# ProDoc__-2026-03-25.net
KiCad netlist of a schematic drawn in EasyEDA Pro
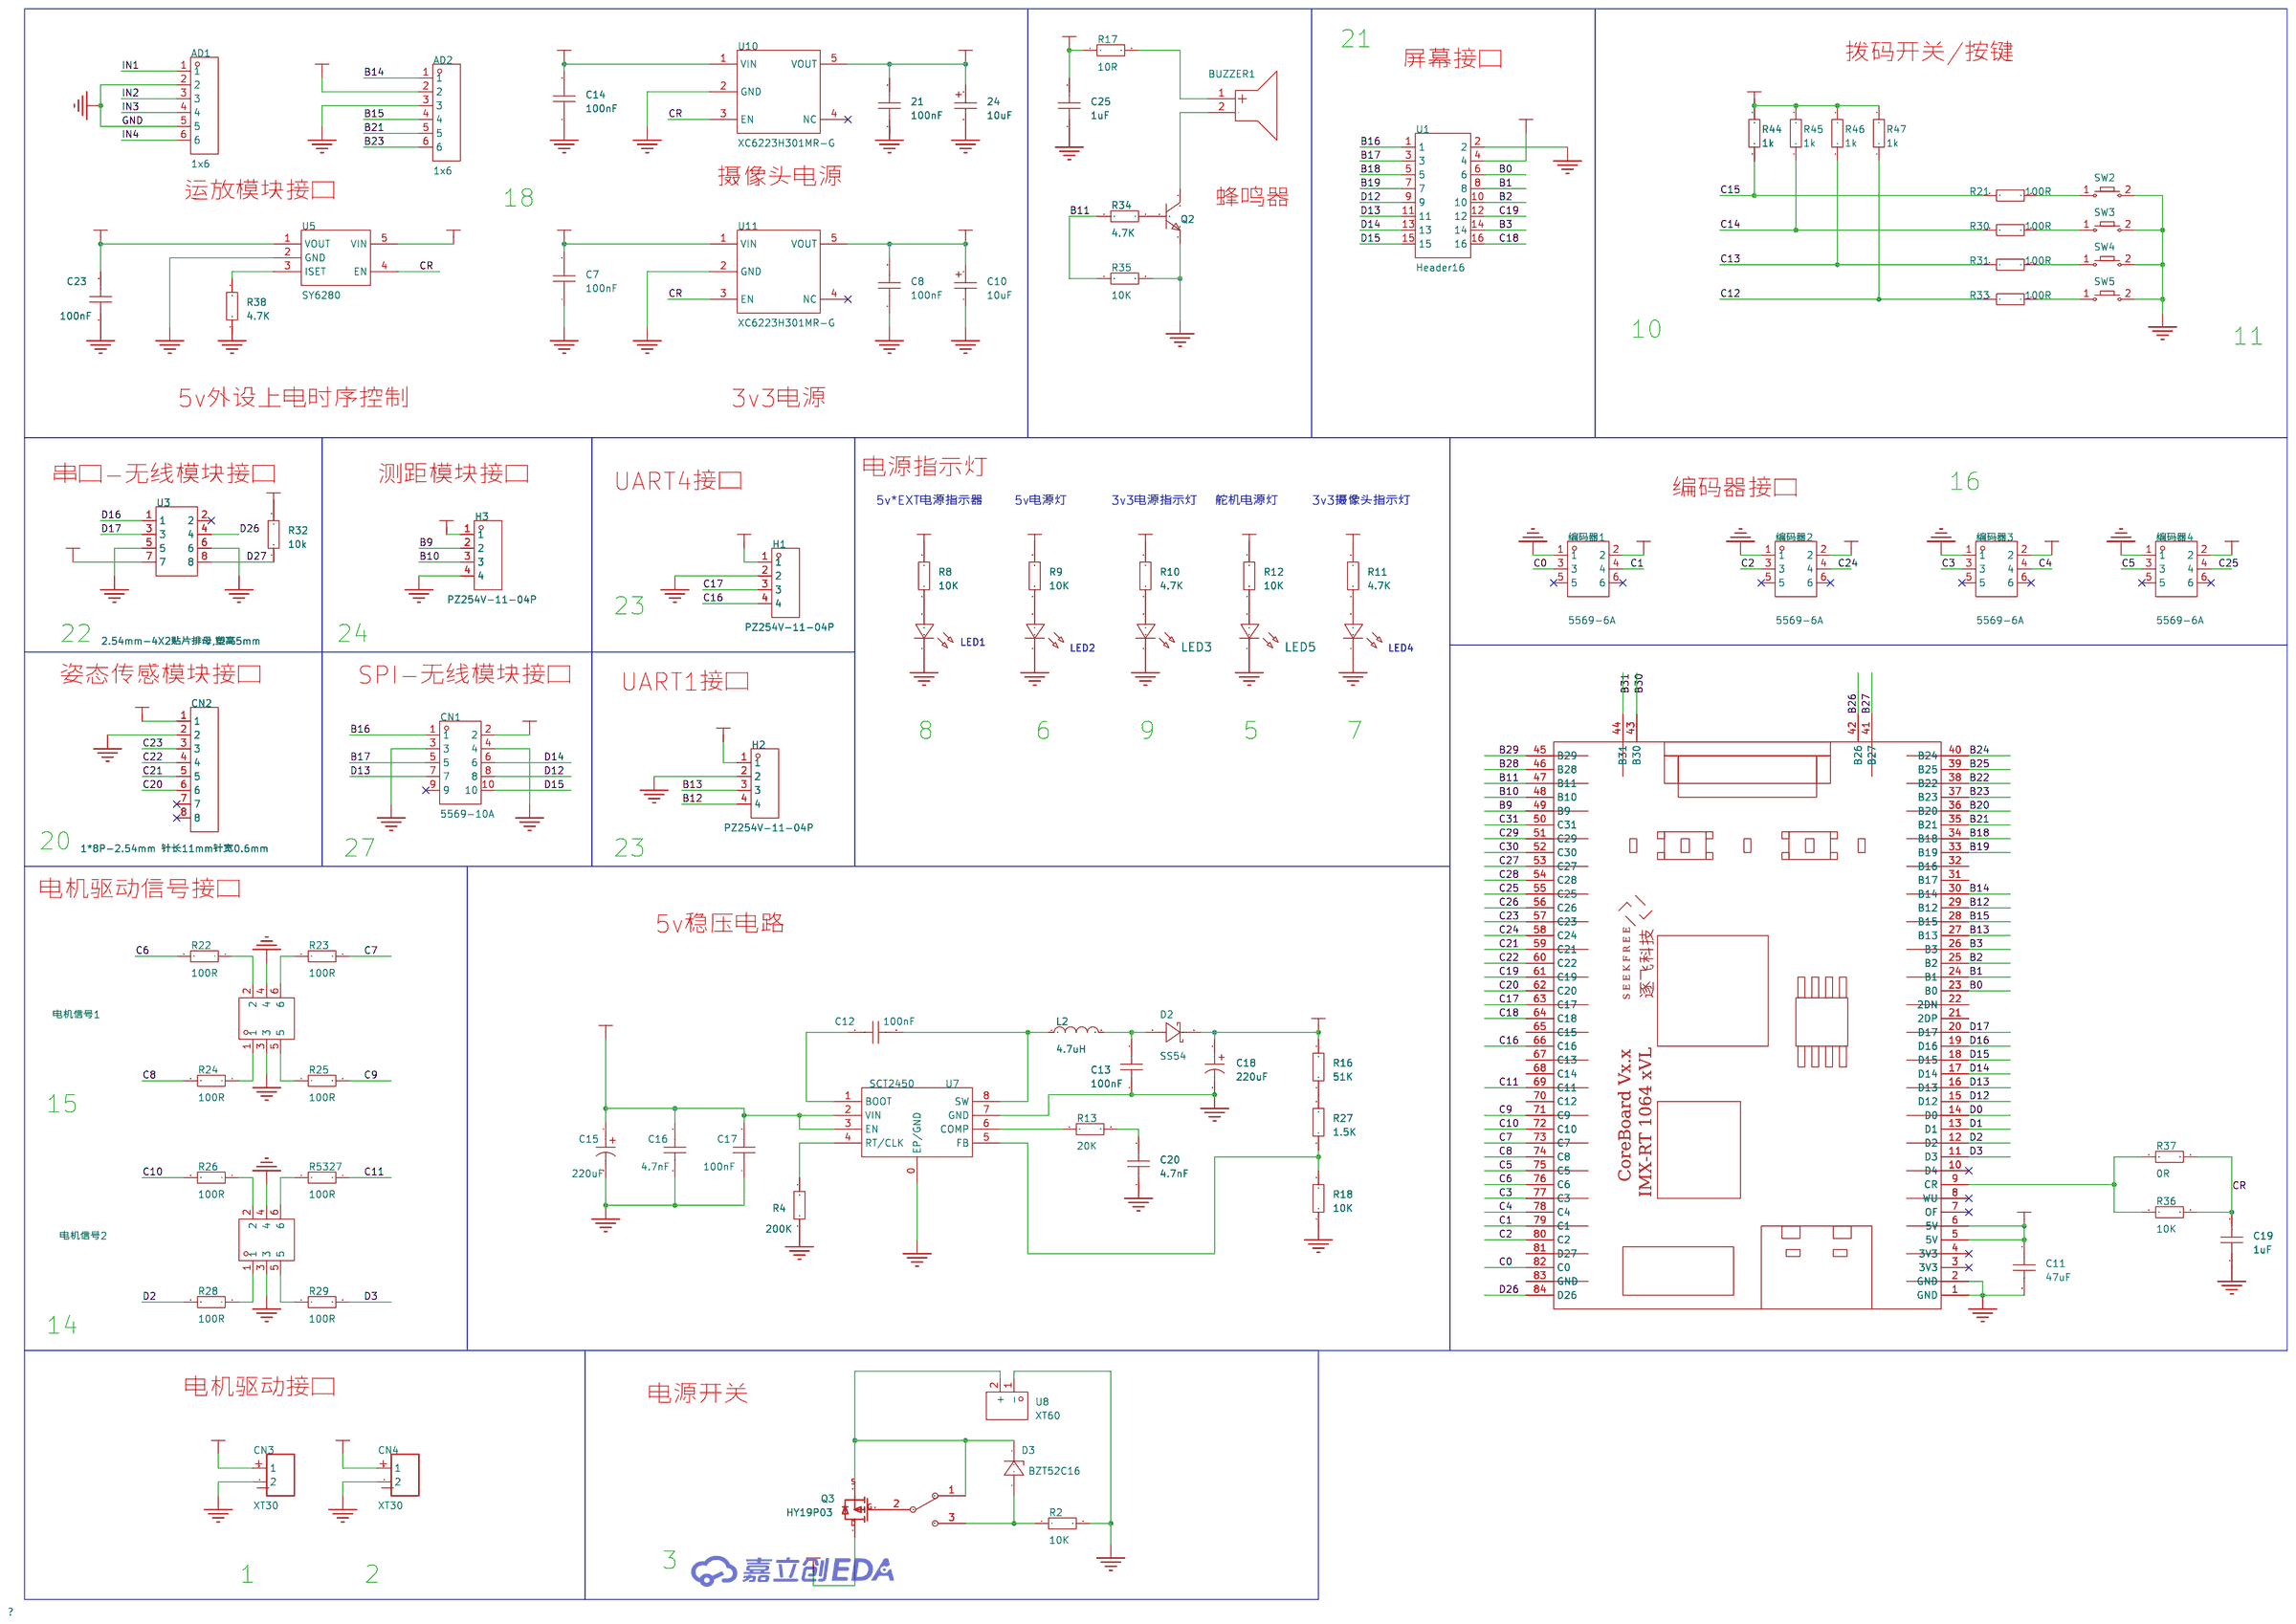
[diagram p0: schematic sheet]

(export (version "E")
  (design (tool "Eeschema 10.0.6"))
  (components
    (comp (ref "21")
      (value "100nF")
      (footprint "easyedapro:C0603")
      (libsource (lib "easyedapro") (part "Capacitance"))
    )
    (comp (ref "24")
      (value "10uF")
      (footprint "easyedapro:CAP-SMD_L3.2-W1.6-RD-C7171")
      (description "容值:10uF;精度:±10%;额定电压:16V;等效串联电阻(ESR):3Ω@100kHz;")
      (fields (field (name "Manufacturer Part") "TAJA106K016RNJ") (field (name "Manufacturer") "Kyocera AVX"))
      (libsource (lib "easyedapro") (part "TAJA106K016RNJ"))
    )
    (comp (ref "AD1")
      (value "1x6")
      (footprint "easyedapro:HDR-TH_6P-P2.54-V-F")
      (fields (field (name "Manufacturer Part") "Female header 1*6p") (field (name "Manufacturer") "BOOMELE"))
      (libsource (lib "easyedapro") (part "1x6"))
    )
    (comp (ref "AD2")
      (value "1x6")
      (footprint "easyedapro:HDR-TH_6P-P2.54-V-F")
      (fields (field (name "Manufacturer Part") "Female header 1*6p") (field (name "Manufacturer") "BOOMELE"))
      (libsource (lib "easyedapro") (part "1x6"))
    )
    (comp (ref "BUZZER1")
      (value "5V,管脚间距8mm,外径10mm,高9.5mm")
      (footprint "easyedapro:BUZ-TH_BD12.0-P7.60-D0.6-FD")
      (libsource (lib "easyedapro") (part "5V,管脚间距8MM,外径10MM,高9.5MM"))
    )
    (comp (ref "C7")
      (value "100nF")
      (footprint "easyedapro:C0603")
      (libsource (lib "easyedapro") (part "Capacitance"))
    )
    (comp (ref "C8")
      (value "100nF")
      (footprint "easyedapro:C0603")
      (libsource (lib "easyedapro") (part "Capacitance"))
    )
    (comp (ref "C10")
      (value "10uF")
      (footprint "easyedapro:CAP-SMD_L3.2-W1.6-RD-C7171")
      (description "容值:10uF;精度:±10%;额定电压:16V;等效串联电阻(ESR):3Ω@100kHz;")
      (fields (field (name "Manufacturer Part") "TAJA106K016RNJ") (field (name "Manufacturer") "Kyocera AVX"))
      (libsource (lib "easyedapro") (part "TAJA106K016RNJ"))
    )
    (comp (ref "C11")
      (value "47uF")
      (footprint "easyedapro:C0603")
      (libsource (lib "easyedapro") (part "Capacitance"))
    )
    (comp (ref "C12")
      (value "100nF")
      (footprint "easyedapro:C0603")
      (libsource (lib "easyedapro") (part "Capacitance"))
    )
    (comp (ref "C13")
      (value "100nF")
      (footprint "easyedapro:C1206")
      (libsource (lib "easyedapro") (part "Capacitance"))
    )
    (comp (ref "C14")
      (value "100nF")
      (footprint "easyedapro:C0603")
      (libsource (lib "easyedapro") (part "Capacitance"))
    )
    (comp (ref "C15")
      (value "220uF")
      (footprint "easyedapro:CAP-SMD_BD8.0-L8.3-W8.3-LS9.0-FD")
      (description "容值:220uF;精度:±20%;额定电压:25V;纹波电流:183mA@120Hz;")
      (fields
        (field (name "Manufacturer Part") "RYRVT25V220UF8*10")
        (field (name "Manufacturer") "HONOR(荣誉)")
      )
      (libsource (lib "easyedapro") (part "RYRVT25V220UF8*10"))
    )
    (comp (ref "C16")
      (value "4.7nF")
      (footprint "easyedapro:C1206")
      (libsource (lib "easyedapro") (part "Capacitance"))
    )
    (comp (ref "C17")
      (value "100nF")
      (footprint "easyedapro:C0603")
      (libsource (lib "easyedapro") (part "Capacitance"))
    )
    (comp (ref "C18")
      (value "220uF")
      (footprint "easyedapro:CAP-SMD_BD8.0-L8.3-W8.3-LS9.0-FD")
      (description "容值:220uF;精度:±20%;额定电压:25V;纹波电流:183mA@120Hz;")
      (fields
        (field (name "Manufacturer Part") "RYRVT25V220UF8*10")
        (field (name "Manufacturer") "HONOR(荣誉)")
      )
      (libsource (lib "easyedapro") (part "RYRVT25V220UF8*10"))
    )
    (comp (ref "C19")
      (value "1uF")
      (footprint "easyedapro:C0603")
      (libsource (lib "easyedapro") (part "Capacitance"))
    )
    (comp (ref "C20")
      (value "4.7nF")
      (footprint "easyedapro:C0603")
      (libsource (lib "easyedapro") (part "Capacitance"))
    )
    (comp (ref "C23")
      (value "100nF")
      (footprint "easyedapro:C0603")
      (libsource (lib "easyedapro") (part "Capacitance"))
    )
    (comp (ref "C25")
      (value "1uF")
      (footprint "easyedapro:C0603")
      (libsource (lib "easyedapro") (part "Capacitance"))
    )
    (comp (ref "CN1")
      (value "5569-10A")
      (footprint "easyedapro:CONN-TH_10P-P4.20_5569-10A")
      (libsource (lib "easyedapro") (part "5569-10A"))
    )
    (comp (ref "CN2")
      (value "1*8P-2.54mm 针长11mm针宽0.6mm")
      (footprint "easyedapro:HDR-TH_8P-P2.54-V-F-S2.54")
      (libsource (lib "easyedapro") (part "1*8P-2.54MM 针长11MM针宽0.6MM"))
    )
    (comp (ref "CN3")
      (value "XT30")
      (footprint "easyedapro:XT30 -WS母头")
      (fields
        (field (name "Manufacturer Part") "XT30UPB-F")
        (field (name "Manufacturer") "Changzhou Amass Elec")
      )
      (libsource (lib "easyedapro") (part "XT30"))
    )
    (comp (ref "CN4")
      (value "XT30")
      (footprint "easyedapro:XT30 -WS母头")
      (fields
        (field (name "Manufacturer Part") "XT30UPB-F")
        (field (name "Manufacturer") "Changzhou Amass Elec")
      )
      (libsource (lib "easyedapro") (part "XT30"))
    )
    (comp (ref "D2")
      (value "SS54")
      (footprint "easyedapro:SMA_L4.2-W2.6-LS5.1-RD")
      (libsource (lib "easyedapro") (part "SS54_C9900023219"))
    )
    (comp (ref "D3")
      (value "BZT52C16")
      (footprint "easyedapro:SOD-123-L")
      (libsource (lib "easyedapro") (part "Diode Zen"))
    )
    (comp (ref "H1")
      (value "PZ254V-11-04P")
      (footprint "easyedapro:HDR-TH_4P-P2.54-V-M")
      (fields (field (name "Manufacturer") "XFCN(兴飞)"))
      (libsource (lib "easyedapro") (part "PZ254V-11-04P_C2691448"))
    )
    (comp (ref "H2")
      (value "PZ254V-11-04P")
      (footprint "easyedapro:HDR-TH_4P-P2.54-V-M")
      (fields (field (name "Manufacturer") "XFCN(兴飞)"))
      (libsource (lib "easyedapro") (part "PZ254V-11-04P_C2691448"))
    )
    (comp (ref "H3")
      (value "PZ254V-11-04P")
      (footprint "easyedapro:HDR-TH_4P-P2.54-V-M")
      (fields (field (name "Manufacturer") "XFCN(兴飞)"))
      (libsource (lib "easyedapro") (part "PZ254V-11-04P_C2691448"))
    )
    (comp (ref "L2")
      (value "4.7uH")
      (footprint "easyedapro:IND-SMD_L7.1-W6.6_POHS0603")
      (description "电感值:4.7uH;精度:±20%;额定电流:5A;饱和电流(Isat):8A;类型:一体成型电感;")
      (fields
        (field (name "Manufacturer Part") "POHS0603-4R7M")
        (field (name "Manufacturer") "HYHONGYEX(宏业)")
      )
      (libsource (lib "easyedapro") (part "POHS0603-4R7M"))
    )
    (comp (ref "LED1")
      (value "~")
      (footprint "easyedapro:LED_0603")
      (libsource (lib "easyedapro") (part "LED_G"))
    )
    (comp (ref "LED2")
      (value "~")
      (footprint "easyedapro:LED_0603")
      (libsource (lib "easyedapro") (part "LED_B"))
    )
    (comp (ref "LED3")
      (value "~")
      (footprint "easyedapro:LED_0603")
      (libsource (lib "easyedapro") (part "LED_R"))
    )
    (comp (ref "LED4")
      (value "~")
      (footprint "easyedapro:LED_0603")
      (libsource (lib "easyedapro") (part "LED_G"))
    )
    (comp (ref "LED5")
      (value "~")
      (footprint "easyedapro:LED_0603")
      (libsource (lib "easyedapro") (part "LED_R"))
    )
    (comp (ref "Q2")
      (value "~")
      (footprint "easyedapro:S8050_TO_92")
      (libsource (lib "easyedapro") (part "S8050_TO_NPN"))
    )
    (comp (ref "Q3")
      (value "HY19P03")
      (footprint "easyedapro:TO-252AA")
      (description "HY19P03 P-Channel MOSFET")
      (libsource (lib "easyedapro") (part "HY19P03"))
    )
    (comp (ref "R2") (value "10K") (footprint "easyedapro:R0603") (libsource (lib "easyedapro") (part "电阻")))
    (comp (ref "R4") (value "200K") (footprint "easyedapro:R0603") (libsource (lib "easyedapro") (part "电阻")))
    (comp (ref "R8") (value "10K") (footprint "easyedapro:R0603") (libsource (lib "easyedapro") (part "电阻")))
    (comp (ref "R9") (value "10K") (footprint "easyedapro:R0603") (libsource (lib "easyedapro") (part "电阻")))
    (comp (ref "R10")
      (value "4.7K")
      (footprint "easyedapro:R0603")
      (libsource (lib "easyedapro") (part "电阻"))
    )
    (comp (ref "R11")
      (value "4.7K")
      (footprint "easyedapro:R0603")
      (libsource (lib "easyedapro") (part "电阻"))
    )
    (comp (ref "R12") (value "10K") (footprint "easyedapro:R0603") (libsource (lib "easyedapro") (part "电阻")))
    (comp (ref "R13") (value "20K") (footprint "easyedapro:R0603") (libsource (lib "easyedapro") (part "电阻")))
    (comp (ref "R16") (value "51K") (footprint "easyedapro:R0603") (libsource (lib "easyedapro") (part "电阻")))
    (comp (ref "R17") (value "10R") (footprint "easyedapro:R0603") (libsource (lib "easyedapro") (part "电阻")))
    (comp (ref "R18") (value "10K") (footprint "easyedapro:R0603") (libsource (lib "easyedapro") (part "电阻")))
    (comp (ref "R21")
      (value "100Ω ±1% 62.5mW")
      (footprint "easyedapro:R0402")
      (fields
        (field (name "Manufacturer Part") "0402WGF1000TCE")
        (field (name "Manufacturer") "UNI-ROYAL(厚声)")
      )
      (libsource (lib "easyedapro") (part "0402WGF1000TCE"))
    )
    (comp (ref "R22")
      (value "100Ω ±1% 62.5mW")
      (footprint "easyedapro:R0402")
      (fields
        (field (name "Manufacturer Part") "0402WGF1000TCE")
        (field (name "Manufacturer") "UNI-ROYAL(厚声)")
      )
      (libsource (lib "easyedapro") (part "0402WGF1000TCE"))
    )
    (comp (ref "R23")
      (value "100Ω ±1% 62.5mW")
      (footprint "easyedapro:R0402")
      (fields
        (field (name "Manufacturer Part") "0402WGF1000TCE")
        (field (name "Manufacturer") "UNI-ROYAL(厚声)")
      )
      (libsource (lib "easyedapro") (part "0402WGF1000TCE"))
    )
    (comp (ref "R24")
      (value "100Ω ±1% 62.5mW")
      (footprint "easyedapro:R0402")
      (fields
        (field (name "Manufacturer Part") "0402WGF1000TCE")
        (field (name "Manufacturer") "UNI-ROYAL(厚声)")
      )
      (libsource (lib "easyedapro") (part "0402WGF1000TCE"))
    )
    (comp (ref "R25")
      (value "100Ω ±1% 62.5mW")
      (footprint "easyedapro:R0402")
      (fields
        (field (name "Manufacturer Part") "0402WGF1000TCE")
        (field (name "Manufacturer") "UNI-ROYAL(厚声)")
      )
      (libsource (lib "easyedapro") (part "0402WGF1000TCE"))
    )
    (comp (ref "R26")
      (value "100Ω ±1% 62.5mW")
      (footprint "easyedapro:R0402")
      (fields
        (field (name "Manufacturer Part") "0402WGF1000TCE")
        (field (name "Manufacturer") "UNI-ROYAL(厚声)")
      )
      (libsource (lib "easyedapro") (part "0402WGF1000TCE"))
    )
    (comp (ref "R27")
      (value "1.5K")
      (footprint "easyedapro:R0603")
      (libsource (lib "easyedapro") (part "电阻"))
    )
    (comp (ref "R28")
      (value "100Ω ±1% 62.5mW")
      (footprint "easyedapro:R0402")
      (fields
        (field (name "Manufacturer Part") "0402WGF1000TCE")
        (field (name "Manufacturer") "UNI-ROYAL(厚声)")
      )
      (libsource (lib "easyedapro") (part "0402WGF1000TCE"))
    )
    (comp (ref "R29")
      (value "100Ω ±1% 62.5mW")
      (footprint "easyedapro:R0402")
      (fields
        (field (name "Manufacturer Part") "0402WGF1000TCE")
        (field (name "Manufacturer") "UNI-ROYAL(厚声)")
      )
      (libsource (lib "easyedapro") (part "0402WGF1000TCE"))
    )
    (comp (ref "R30")
      (value "100Ω ±1% 62.5mW")
      (footprint "easyedapro:R0402")
      (fields
        (field (name "Manufacturer Part") "0402WGF1000TCE")
        (field (name "Manufacturer") "UNI-ROYAL(厚声)")
      )
      (libsource (lib "easyedapro") (part "0402WGF1000TCE"))
    )
    (comp (ref "R31")
      (value "100Ω ±1% 62.5mW")
      (footprint "easyedapro:R0402")
      (fields
        (field (name "Manufacturer Part") "0402WGF1000TCE")
        (field (name "Manufacturer") "UNI-ROYAL(厚声)")
      )
      (libsource (lib "easyedapro") (part "0402WGF1000TCE"))
    )
    (comp (ref "R32")
      (value "10k")
      (footprint "easyedapro:R0603")
      (description "电阻类型:厚膜电阻;阻值:10kΩ;精度:±1%;功率:100mW;工作电压:75V;温度系数:±100ppm/°C;")
      (fields
        (field (name "Manufacturer Part") "0603WAF1002T5E")
        (field (name "Manufacturer") "UNI-ROYAL(厚声)")
      )
      (libsource (lib "easyedapro") (part "0603WAF1002T5E"))
    )
    (comp (ref "R33")
      (value "100Ω ±1% 62.5mW")
      (footprint "easyedapro:R0402")
      (fields
        (field (name "Manufacturer Part") "0402WGF1000TCE")
        (field (name "Manufacturer") "UNI-ROYAL(厚声)")
      )
      (libsource (lib "easyedapro") (part "0402WGF1000TCE"))
    )
    (comp (ref "R34")
      (value "4.7K")
      (footprint "easyedapro:R0603")
      (libsource (lib "easyedapro") (part "电阻"))
    )
    (comp (ref "R35") (value "10K") (footprint "easyedapro:R0603") (libsource (lib "easyedapro") (part "电阻")))
    (comp (ref "R36") (value "10K") (footprint "easyedapro:R0603") (libsource (lib "easyedapro") (part "电阻")))
    (comp (ref "R37") (value "0R") (footprint "easyedapro:R0603") (libsource (lib "easyedapro") (part "电阻")))
    (comp (ref "R38")
      (value "4.7K")
      (footprint "easyedapro:R0603")
      (libsource (lib "easyedapro") (part "电阻"))
    )
    (comp (ref "R44")
      (value "1k")
      (footprint "easyedapro:R0603")
      (description "电阻类型:厚膜电阻;阻值:10kΩ;精度:±1%;功率:100mW;工作电压:75V;温度系数:±100ppm/°C;")
      (fields
        (field (name "Manufacturer Part") "0603WAF1002T5E")
        (field (name "Manufacturer") "UNI-ROYAL(厚声)")
      )
      (libsource (lib "easyedapro") (part "0603WAF1002T5E"))
    )
    (comp (ref "R45")
      (value "1k")
      (footprint "easyedapro:R0603")
      (description "电阻类型:厚膜电阻;阻值:10kΩ;精度:±1%;功率:100mW;工作电压:75V;温度系数:±100ppm/°C;")
      (fields
        (field (name "Manufacturer Part") "0603WAF1002T5E")
        (field (name "Manufacturer") "UNI-ROYAL(厚声)")
      )
      (libsource (lib "easyedapro") (part "0603WAF1002T5E"))
    )
    (comp (ref "R46")
      (value "1k")
      (footprint "easyedapro:R0603")
      (description "电阻类型:厚膜电阻;阻值:10kΩ;精度:±1%;功率:100mW;工作电压:75V;温度系数:±100ppm/°C;")
      (fields
        (field (name "Manufacturer Part") "0603WAF1002T5E")
        (field (name "Manufacturer") "UNI-ROYAL(厚声)")
      )
      (libsource (lib "easyedapro") (part "0603WAF1002T5E"))
    )
    (comp (ref "R47")
      (value "1k")
      (footprint "easyedapro:R0603")
      (description "电阻类型:厚膜电阻;阻值:10kΩ;精度:±1%;功率:100mW;工作电压:75V;温度系数:±100ppm/°C;")
      (fields
        (field (name "Manufacturer Part") "0603WAF1002T5E")
        (field (name "Manufacturer") "UNI-ROYAL(厚声)")
      )
      (libsource (lib "easyedapro") (part "0603WAF1002T5E"))
    )
    (comp (ref "R5327")
      (value "100Ω ±1% 62.5mW")
      (footprint "easyedapro:R0402")
      (fields
        (field (name "Manufacturer Part") "0402WGF1000TCE")
        (field (name "Manufacturer") "UNI-ROYAL(厚声)")
      )
      (libsource (lib "easyedapro") (part "0402WGF1000TCE"))
    )
    (comp (ref "SW2")
      (value "~")
      (footprint "easyedapro:Key_SMD_3x4x2")
      (libsource (lib "easyedapro") (part "轻触按键x2"))
    )
    (comp (ref "SW3")
      (value "~")
      (footprint "easyedapro:Key_SMD_3x4x2")
      (libsource (lib "easyedapro") (part "轻触按键x2"))
    )
    (comp (ref "SW4")
      (value "~")
      (footprint "easyedapro:Key_SMD_3x4x2")
      (libsource (lib "easyedapro") (part "轻触按键x2"))
    )
    (comp (ref "SW5")
      (value "~")
      (footprint "easyedapro:Key_SMD_3x4x2")
      (libsource (lib "easyedapro") (part "轻触按键x2"))
    )
    (comp (ref "SW6")
      (value "拨码开关")
      (footprint "easyedapro:3PIN2档拨动开关")
      (libsource (lib "easyedapro") (part "1路滑动开关"))
    )
    (comp (ref "U1")
      (value "Header16")
      (footprint "easyedapro:CONN-TH_16P-P2.50_C9900044747")
      (libsource (lib "easyedapro") (part "HEADER16_C9900044747"))
    )
    (comp (ref "U3")
      (value "2.54mm-4X2贴片排母,塑高5mm")
      (footprint "easyedapro:HDR-SMD_8P-P2.54-V-F-R2-C4-S7.1")
      (libsource (lib "easyedapro") (part "2.54MM-4X2贴片排母,塑高5MM"))
    )
    (comp (ref "U5")
      (value "SY6280")
      (footprint "easyedapro:SOT-23-5")
      (libsource (lib "easyedapro") (part "SY6280"))
    )
    (comp (ref "U7")
      (value "SCT2450")
      (footprint "easyedapro:SOP-8E")
      (libsource (lib "easyedapro") (part "SCT2450"))
    )
    (comp (ref "U8")
      (value "XT60")
      (footprint "easyedapro:CONN-TH_XT60")
      (description "模型锂电连接器")
      (fields (field (name "Manufacturer") "AMASS(艾迈斯)"))
      (libsource (lib "easyedapro") (part "XT60"))
    )
    (comp (ref "U10")
      (value "XC6223H301MR-G")
      (footprint "easyedapro:SOT_235")
      (libsource (lib "easyedapro") (part "RT9013"))
    )
    (comp (ref "U11")
      (value "XC6223H301MR-G")
      (footprint "easyedapro:SOT_235")
      (libsource (lib "easyedapro") (part "RT9013"))
    )
    (comp (ref "U?1")
      (value "~")
      (footprint "easyedapro:AUFE_RT1064")
      (libsource (lib "easyedapro") (part "RT1064"))
    )
    (comp (ref "电机信号1")
      (value "5569-6A")
      (footprint "easyedapro:CONN-TH_6P-P4.20_5569-6A-1")
      (libsource (lib "easyedapro") (part "5569-6A"))
    )
    (comp (ref "电机信号2")
      (value "5569-6A")
      (footprint "easyedapro:CONN-TH_6P-P4.20_5569-6A-1")
      (libsource (lib "easyedapro") (part "5569-6A"))
    )
    (comp (ref "编码器1")
      (value "5569-6A")
      (footprint "easyedapro:CONN-TH_6P-P4.20_5569-6A-1")
      (libsource (lib "easyedapro") (part "5569-6A"))
    )
    (comp (ref "编码器2")
      (value "5569-6A")
      (footprint "easyedapro:CONN-TH_6P-P4.20_5569-6A-1")
      (libsource (lib "easyedapro") (part "5569-6A"))
    )
    (comp (ref "编码器3")
      (value "5569-6A")
      (footprint "easyedapro:CONN-TH_6P-P4.20_5569-6A-1")
      (libsource (lib "easyedapro") (part "5569-6A"))
    )
    (comp (ref "编码器4")
      (value "5569-6A")
      (footprint "easyedapro:CONN-TH_6P-P4.20_5569-6A-1")
      (libsource (lib "easyedapro") (part "5569-6A"))
    )
  )
  (nets
    (net (code "1") (name "/B0") (class "Default")
      (node (ref "U1") (pin "6") (pinfunction "6_6") (pintype "unspecified"))
      (node (ref "U?1") (pin "23") (pinfunction "B0_23") (pintype "input"))
    )
    (net (code "2") (name "/B1") (class "Default")
      (node (ref "U1") (pin "8") (pinfunction "8_8") (pintype "unspecified"))
      (node (ref "U?1") (pin "24") (pinfunction "B1_24") (pintype "input"))
    )
    (net (code "3") (name "/B2") (class "Default")
      (node (ref "U1") (pin "10") (pinfunction "10_10") (pintype "unspecified"))
      (node (ref "U?1") (pin "25") (pinfunction "B2_25") (pintype "input"))
    )
    (net (code "4") (name "/B3") (class "Default")
      (node (ref "U1") (pin "14") (pinfunction "14_14") (pintype "unspecified"))
      (node (ref "U?1") (pin "26") (pinfunction "B3_26") (pintype "input"))
    )
    (net (code "5") (name "/B9") (class "Default")
      (node (ref "H3") (pin "2") (pinfunction "2_2") (pintype "unspecified"))
      (node (ref "U?1") (pin "49") (pinfunction "B9_49") (pintype "input"))
    )
    (net (code "6") (name "/B10") (class "Default")
      (node (ref "H3") (pin "3") (pinfunction "3_3") (pintype "unspecified"))
      (node (ref "U?1") (pin "48") (pinfunction "B10_48") (pintype "input"))
    )
    (net (code "7") (name "/B11") (class "Default")
      (node (ref "R34") (pin "1") (pinfunction "1_1") (pintype "input"))
      (node (ref "R35") (pin "1") (pinfunction "1_1") (pintype "input"))
      (node (ref "U?1") (pin "47") (pinfunction "B11_47") (pintype "input"))
    )
    (net (code "8") (name "/B12") (class "Default")
      (node (ref "H2") (pin "4") (pinfunction "4_4") (pintype "unspecified"))
      (node (ref "U?1") (pin "29") (pinfunction "B12_29") (pintype "input"))
    )
    (net (code "9") (name "/B13") (class "Default")
      (node (ref "H2") (pin "3") (pinfunction "3_3") (pintype "unspecified"))
      (node (ref "U?1") (pin "27") (pinfunction "B13_27") (pintype "input"))
    )
    (net (code "10") (name "/B14") (class "Default")
      (node (ref "AD2") (pin "1") (pinfunction "1_1") (pintype "unspecified"))
      (node (ref "U?1") (pin "30") (pinfunction "B14_30") (pintype "input"))
    )
    (net (code "11") (name "/B15") (class "Default")
      (node (ref "AD2") (pin "4") (pinfunction "4_4") (pintype "unspecified"))
      (node (ref "U?1") (pin "28") (pinfunction "B15_28") (pintype "input"))
    )
    (net (code "12") (name "/B16") (class "Default")
      (node (ref "CN1") (pin "1") (pinfunction "1_1") (pintype "unspecified"))
      (node (ref "U1") (pin "1") (pinfunction "1_1") (pintype "unspecified"))
    )
    (net (code "13") (name "/B17") (class "Default")
      (node (ref "CN1") (pin "5") (pinfunction "5_5") (pintype "unspecified"))
      (node (ref "U1") (pin "3") (pinfunction "3_3") (pintype "unspecified"))
    )
    (net (code "14") (name "/B18") (class "Default")
      (node (ref "U1") (pin "5") (pinfunction "5_5") (pintype "unspecified"))
      (node (ref "U?1") (pin "34") (pinfunction "B18_34") (pintype "input"))
    )
    (net (code "15") (name "/B19") (class "Default")
      (node (ref "U1") (pin "7") (pinfunction "7_7") (pintype "unspecified"))
      (node (ref "U?1") (pin "33") (pinfunction "B19_33") (pintype "input"))
    )
    (net (code "16") (name "/B20") (class "Default")
      (node (ref "U?1") (pin "36") (pinfunction "B20_36") (pintype "input"))
    )
    (net (code "17") (name "/B21") (class "Default")
      (node (ref "AD2") (pin "5") (pinfunction "5_5") (pintype "unspecified"))
      (node (ref "U?1") (pin "35") (pinfunction "B21_35") (pintype "input"))
    )
    (net (code "18") (name "/B22") (class "Default")
      (node (ref "U?1") (pin "38") (pinfunction "B22_38") (pintype "input"))
    )
    (net (code "19") (name "/B23") (class "Default")
      (node (ref "AD2") (pin "6") (pinfunction "6_6") (pintype "unspecified"))
      (node (ref "U?1") (pin "37") (pinfunction "B23_37") (pintype "input"))
    )
    (net (code "20") (name "/B24") (class "Default")
      (node (ref "U?1") (pin "40") (pinfunction "B24_40") (pintype "input"))
    )
    (net (code "21") (name "/B25") (class "Default")
      (node (ref "U?1") (pin "39") (pinfunction "B25_39") (pintype "input"))
    )
    (net (code "22") (name "/B26") (class "Default")
      (node (ref "U?1") (pin "42") (pinfunction "B26_42") (pintype "input"))
    )
    (net (code "23") (name "/B27") (class "Default")
      (node (ref "U?1") (pin "41") (pinfunction "B27_41") (pintype "input"))
    )
    (net (code "24") (name "/B28") (class "Default")
      (node (ref "U?1") (pin "46") (pinfunction "B28_46") (pintype "input"))
    )
    (net (code "25") (name "/B29") (class "Default")
      (node (ref "U?1") (pin "45") (pinfunction "B29_45") (pintype "input"))
    )
    (net (code "26") (name "/B30") (class "Default")
      (node (ref "U?1") (pin "43") (pinfunction "B30_43") (pintype "input"))
    )
    (net (code "27") (name "/B31") (class "Default")
      (node (ref "U?1") (pin "44") (pinfunction "B31_44") (pintype "input"))
    )
    (net (code "28") (name "/C0") (class "Default")
      (node (ref "U?1") (pin "82") (pinfunction "C0_82") (pintype "input"))
      (node (ref "编码器1") (pin "3") (pinfunction "3_3") (pintype "unspecified"))
    )
    (net (code "29") (name "/C1") (class "Default")
      (node (ref "U?1") (pin "79") (pinfunction "C1_79") (pintype "input"))
      (node (ref "编码器1") (pin "4") (pinfunction "4_4") (pintype "unspecified"))
    )
    (net (code "30") (name "/C2") (class "Default")
      (node (ref "U?1") (pin "80") (pinfunction "C2_80") (pintype "input"))
      (node (ref "编码器2") (pin "3") (pinfunction "3_3") (pintype "unspecified"))
    )
    (net (code "31") (name "/C3") (class "Default")
      (node (ref "U?1") (pin "77") (pinfunction "C3_77") (pintype "input"))
      (node (ref "编码器3") (pin "3") (pinfunction "3_3") (pintype "unspecified"))
    )
    (net (code "32") (name "/C4") (class "Default")
      (node (ref "U?1") (pin "78") (pinfunction "C4_78") (pintype "input"))
      (node (ref "编码器3") (pin "4") (pinfunction "4_4") (pintype "unspecified"))
    )
    (net (code "33") (name "/C5") (class "Default")
      (node (ref "U?1") (pin "75") (pinfunction "C5_75") (pintype "input"))
      (node (ref "编码器4") (pin "3") (pinfunction "3_3") (pintype "unspecified"))
    )
    (net (code "34") (name "/C6") (class "Default")
      (node (ref "R22") (pin "2") (pinfunction "2_2") (pintype "input"))
      (node (ref "U?1") (pin "76") (pinfunction "C6_76") (pintype "input"))
    )
    (net (code "35") (name "/C7") (class "Default")
      (node (ref "R23") (pin "1") (pinfunction "1_1") (pintype "input"))
      (node (ref "U?1") (pin "73") (pinfunction "C7_73") (pintype "input"))
    )
    (net (code "36") (name "/C8") (class "Default")
      (node (ref "R24") (pin "2") (pinfunction "2_2") (pintype "input"))
      (node (ref "U?1") (pin "74") (pinfunction "C8_74") (pintype "input"))
    )
    (net (code "37") (name "/C9") (class "Default")
      (node (ref "R25") (pin "2") (pinfunction "2_2") (pintype "input"))
      (node (ref "U?1") (pin "71") (pinfunction "C9_71") (pintype "input"))
    )
    (net (code "38") (name "/C10") (class "Default")
      (node (ref "R26") (pin "2") (pinfunction "2_2") (pintype "input"))
      (node (ref "U?1") (pin "72") (pinfunction "C10_72") (pintype "input"))
    )
    (net (code "39") (name "/C11") (class "Default")
      (node (ref "R5327") (pin "1") (pinfunction "1_1") (pintype "input"))
      (node (ref "U?1") (pin "69") (pinfunction "C11_69") (pintype "input"))
    )
    (net (code "40") (name "/C12") (class "Default")
      (node (ref "R33") (pin "2") (pinfunction "2_2") (pintype "input"))
      (node (ref "R47") (pin "1") (pinfunction "1_1") (pintype "input"))
    )
    (net (code "41") (name "/C13") (class "Default")
      (node (ref "R31") (pin "2") (pinfunction "2_2") (pintype "input"))
      (node (ref "R46") (pin "1") (pinfunction "1_1") (pintype "input"))
    )
    (net (code "42") (name "/C14") (class "Default")
      (node (ref "R30") (pin "2") (pinfunction "2_2") (pintype "input"))
      (node (ref "R45") (pin "1") (pinfunction "1_1") (pintype "input"))
    )
    (net (code "43") (name "/C15") (class "Default")
      (node (ref "R21") (pin "2") (pinfunction "2_2") (pintype "input"))
      (node (ref "R44") (pin "1") (pinfunction "1_1") (pintype "input"))
    )
    (net (code "44") (name "/C16") (class "Default")
      (node (ref "H1") (pin "4") (pinfunction "4_4") (pintype "unspecified"))
      (node (ref "U?1") (pin "66") (pinfunction "C16_66") (pintype "input"))
    )
    (net (code "45") (name "/C17") (class "Default")
      (node (ref "H1") (pin "3") (pinfunction "3_3") (pintype "unspecified"))
      (node (ref "U?1") (pin "63") (pinfunction "C17_63") (pintype "input"))
    )
    (net (code "46") (name "/C18") (class "Default")
      (node (ref "U1") (pin "16") (pinfunction "16_16") (pintype "unspecified"))
      (node (ref "U?1") (pin "64") (pinfunction "C18_64") (pintype "input"))
    )
    (net (code "47") (name "/C19") (class "Default")
      (node (ref "U1") (pin "12") (pinfunction "12_12") (pintype "unspecified"))
      (node (ref "U?1") (pin "61") (pinfunction "C19_61") (pintype "input"))
    )
    (net (code "48") (name "/C20") (class "Default")
      (node (ref "CN2") (pin "6") (pinfunction "6_6") (pintype "unspecified"))
      (node (ref "U?1") (pin "62") (pinfunction "C20_62") (pintype "input"))
    )
    (net (code "49") (name "/C21") (class "Default")
      (node (ref "CN2") (pin "5") (pinfunction "5_5") (pintype "unspecified"))
      (node (ref "U?1") (pin "59") (pinfunction "C21_59") (pintype "input"))
    )
    (net (code "50") (name "/C22") (class "Default")
      (node (ref "CN2") (pin "4") (pinfunction "4_4") (pintype "unspecified"))
      (node (ref "U?1") (pin "60") (pinfunction "C22_60") (pintype "input"))
    )
    (net (code "51") (name "/C23") (class "Default")
      (node (ref "CN2") (pin "3") (pinfunction "3_3") (pintype "unspecified"))
      (node (ref "U?1") (pin "57") (pinfunction "C23_57") (pintype "input"))
    )
    (net (code "52") (name "/C24") (class "Default")
      (node (ref "U?1") (pin "58") (pinfunction "C24_58") (pintype "input"))
      (node (ref "编码器2") (pin "4") (pinfunction "4_4") (pintype "unspecified"))
    )
    (net (code "53") (name "/C25") (class "Default")
      (node (ref "U?1") (pin "55") (pinfunction "C25_55") (pintype "input"))
      (node (ref "编码器4") (pin "4") (pinfunction "4_4") (pintype "unspecified"))
    )
    (net (code "54") (name "/C26") (class "Default")
      (node (ref "U?1") (pin "56") (pinfunction "C26_56") (pintype "input"))
    )
    (net (code "55") (name "/C27") (class "Default")
      (node (ref "U?1") (pin "53") (pinfunction "C27_53") (pintype "input"))
    )
    (net (code "56") (name "/C28") (class "Default")
      (node (ref "U?1") (pin "54") (pinfunction "C28_54") (pintype "input"))
    )
    (net (code "57") (name "/C29") (class "Default")
      (node (ref "U?1") (pin "51") (pinfunction "C29_51") (pintype "input"))
    )
    (net (code "58") (name "/C30") (class "Default")
      (node (ref "U?1") (pin "52") (pinfunction "C30_52") (pintype "input"))
    )
    (net (code "59") (name "/C31") (class "Default")
      (node (ref "U?1") (pin "50") (pinfunction "C31_50") (pintype "input"))
    )
    (net (code "60") (name "/CR") (class "Default")
      (node (ref "C19") (pin "2") (pinfunction "2_2") (pintype "input"))
      (node (ref "R36") (pin "2") (pinfunction "2_2") (pintype "input"))
      (node (ref "R37") (pin "2") (pinfunction "2_2") (pintype "input"))
      (node (ref "U10") (pin "3") (pinfunction "EN_3") (pintype "unspecified"))
      (node (ref "U11") (pin "3") (pinfunction "EN_3") (pintype "unspecified"))
      (node (ref "U5") (pin "4") (pinfunction "EN_4") (pintype "unspecified"))
    )
    (net (code "61") (name "/D0") (class "Default")
      (node (ref "U?1") (pin "14") (pinfunction "D0_14") (pintype "input"))
    )
    (net (code "62") (name "/D1") (class "Default")
      (node (ref "U?1") (pin "13") (pinfunction "D1_13") (pintype "input"))
    )
    (net (code "63") (name "/D2") (class "Default")
      (node (ref "R28") (pin "2") (pinfunction "2_2") (pintype "input"))
      (node (ref "U?1") (pin "12") (pinfunction "D2_12") (pintype "input"))
    )
    (net (code "64") (name "/D3") (class "Default")
      (node (ref "R29") (pin "2") (pinfunction "2_2") (pintype "input"))
      (node (ref "U?1") (pin "11") (pinfunction "D3_11") (pintype "input"))
    )
    (net (code "65") (name "/D12") (class "Default")
      (node (ref "CN1") (pin "8") (pinfunction "8_8") (pintype "unspecified"))
      (node (ref "U1") (pin "9") (pinfunction "9_9") (pintype "unspecified"))
      (node (ref "U?1") (pin "15") (pinfunction "D12_15") (pintype "input"))
    )
    (net (code "66") (name "/D13") (class "Default")
      (node (ref "CN1") (pin "7") (pinfunction "7_7") (pintype "unspecified"))
      (node (ref "U1") (pin "11") (pinfunction "11_11") (pintype "unspecified"))
      (node (ref "U?1") (pin "16") (pinfunction "D13_16") (pintype "input"))
    )
    (net (code "67") (name "/D14") (class "Default")
      (node (ref "CN1") (pin "6") (pinfunction "6_6") (pintype "unspecified"))
      (node (ref "U1") (pin "13") (pinfunction "13_13") (pintype "unspecified"))
      (node (ref "U?1") (pin "17") (pinfunction "D14_17") (pintype "input"))
    )
    (net (code "68") (name "/D15") (class "Default")
      (node (ref "CN1") (pin "10") (pinfunction "10_10") (pintype "unspecified"))
      (node (ref "U1") (pin "15") (pinfunction "15_15") (pintype "unspecified"))
      (node (ref "U?1") (pin "18") (pinfunction "D15_18") (pintype "input"))
    )
    (net (code "69") (name "/D16") (class "Default")
      (node (ref "U3") (pin "1") (pinfunction "1_1") (pintype "unspecified"))
      (node (ref "U?1") (pin "19") (pinfunction "D16_19") (pintype "input"))
    )
    (net (code "70") (name "/D17") (class "Default")
      (node (ref "U3") (pin "3") (pinfunction "3_3") (pintype "unspecified"))
      (node (ref "U?1") (pin "20") (pinfunction "D17_20") (pintype "input"))
    )
    (net (code "71") (name "/D26") (class "Default")
      (node (ref "U3") (pin "4") (pinfunction "4_4") (pintype "unspecified"))
      (node (ref "U?1") (pin "84") (pinfunction "D26_84") (pintype "input"))
    )
    (net (code "72") (name "/D27") (class "Default")
      (node (ref "R32") (pin "1") (pinfunction "1_1") (pintype "input"))
      (node (ref "U3") (pin "8") (pinfunction "8_8") (pintype "unspecified"))
    )
    (net (code "73") (name "/IN1") (class "Default")
      (node (ref "AD1") (pin "1") (pinfunction "1_1") (pintype "unspecified"))
    )
    (net (code "74") (name "/IN2") (class "Default")
      (node (ref "AD1") (pin "3") (pinfunction "3_3") (pintype "unspecified"))
    )
    (net (code "75") (name "/IN3") (class "Default")
      (node (ref "AD1") (pin "4") (pinfunction "4_4") (pintype "unspecified"))
    )
    (net (code "76") (name "/IN4") (class "Default")
      (node (ref "AD1") (pin "6") (pinfunction "6_6") (pintype "unspecified"))
    )
    (net (code "77") (name "3V3") (class "Default")
      (node (ref "21") (pin "2") (pinfunction "2_2") (pintype "input"))
      (node (ref "24") (pin "1") (pinfunction "1_1") (pintype "input"))
      (node (ref "AD2") (pin "2") (pinfunction "2_2") (pintype "unspecified"))
      (node (ref "C10") (pin "1") (pinfunction "1_1") (pintype "input"))
      (node (ref "C25") (pin "2") (pinfunction "2_2") (pintype "input"))
      (node (ref "C8") (pin "2") (pinfunction "2_2") (pintype "input"))
      (node (ref "CN2") (pin "1") (pinfunction "1_1") (pintype "unspecified"))
      (node (ref "H3") (pin "1") (pinfunction "1_1") (pintype "unspecified"))
      (node (ref "R10") (pin "2") (pinfunction "2_2") (pintype "input"))
      (node (ref "R17") (pin "1") (pinfunction "1_1") (pintype "input"))
      (node (ref "R32") (pin "2") (pinfunction "2_2") (pintype "input"))
      (node (ref "R44") (pin "2") (pinfunction "2_2") (pintype "input"))
      (node (ref "R45") (pin "2") (pinfunction "2_2") (pintype "input"))
      (node (ref "R46") (pin "2") (pinfunction "2_2") (pintype "input"))
      (node (ref "R47") (pin "2") (pinfunction "2_2") (pintype "input"))
      (node (ref "U1") (pin "4") (pinfunction "4_4") (pintype "unspecified"))
      (node (ref "U10") (pin "5") (pinfunction "VOUT_5") (pintype "unspecified"))
      (node (ref "U11") (pin "5") (pinfunction "VOUT_5") (pintype "unspecified"))
      (node (ref "编码器1") (pin "2") (pinfunction "2_2") (pintype "unspecified"))
      (node (ref "编码器2") (pin "2") (pinfunction "2_2") (pintype "unspecified"))
      (node (ref "编码器3") (pin "2") (pinfunction "2_2") (pintype "unspecified"))
      (node (ref "编码器4") (pin "2") (pinfunction "2_2") (pintype "unspecified"))
    )
    (net (code "78") (name "CSI-3V3") (class "Default")
      (node (ref "R11") (pin "2") (pinfunction "2_2") (pintype "input"))
    )
    (net (code "79") (name "GND") (class "Default")
      (node (ref "21") (pin "1") (pinfunction "1_1") (pintype "input"))
      (node (ref "24") (pin "2") (pinfunction "2_2") (pintype "input"))
      (node (ref "AD1") (pin "2") (pinfunction "2_2") (pintype "unspecified"))
      (node (ref "AD1") (pin "5") (pinfunction "5_5") (pintype "unspecified"))
      (node (ref "AD2") (pin "3") (pinfunction "3_3") (pintype "unspecified"))
      (node (ref "C10") (pin "2") (pinfunction "2_2") (pintype "input"))
      (node (ref "C11") (pin "2") (pinfunction "2_2") (pintype "input"))
      (node (ref "C13") (pin "1") (pinfunction "1_1") (pintype "input"))
      (node (ref "C14") (pin "1") (pinfunction "1_1") (pintype "input"))
      (node (ref "C15") (pin "2") (pinfunction "2_2") (pintype "input"))
      (node (ref "C16") (pin "1") (pinfunction "1_1") (pintype "input"))
      (node (ref "C17") (pin "1") (pinfunction "1_1") (pintype "input"))
      (node (ref "C18") (pin "2") (pinfunction "2_2") (pintype "input"))
      (node (ref "C19") (pin "1") (pinfunction "1_1") (pintype "input"))
      (node (ref "C20") (pin "1") (pinfunction "1_1") (pintype "input"))
      (node (ref "C23") (pin "1") (pinfunction "1_1") (pintype "input"))
      (node (ref "C25") (pin "1") (pinfunction "1_1") (pintype "input"))
      (node (ref "C7") (pin "1") (pinfunction "1_1") (pintype "input"))
      (node (ref "C8") (pin "1") (pinfunction "1_1") (pintype "input"))
      (node (ref "CN1") (pin "3") (pinfunction "3_3") (pintype "unspecified"))
      (node (ref "CN1") (pin "4") (pinfunction "4_4") (pintype "unspecified"))
      (node (ref "CN2") (pin "2") (pinfunction "2_2") (pintype "unspecified"))
      (node (ref "CN3") (pin "2") (pinfunction "2_2") (pintype "unspecified"))
      (node (ref "CN4") (pin "2") (pinfunction "2_2") (pintype "unspecified"))
      (node (ref "H1") (pin "2") (pinfunction "2_2") (pintype "unspecified"))
      (node (ref "H2") (pin "2") (pinfunction "2_2") (pintype "unspecified"))
      (node (ref "H3") (pin "4") (pinfunction "4_4") (pintype "unspecified"))
      (node (ref "LED1") (pin "1") (pinfunction "C_1") (pintype "input"))
      (node (ref "LED2") (pin "1") (pinfunction "C_1") (pintype "input"))
      (node (ref "LED3") (pin "1") (pinfunction "C_1") (pintype "input"))
      (node (ref "LED4") (pin "1") (pinfunction "C_1") (pintype "input"))
      (node (ref "LED5") (pin "1") (pinfunction "C_1") (pintype "input"))
      (node (ref "Q2") (pin "1") (pinfunction "E_1") (pintype "unspecified"))
      (node (ref "R18") (pin "1") (pinfunction "1_1") (pintype "input"))
      (node (ref "R2") (pin "2") (pinfunction "2_2") (pintype "input"))
      (node (ref "R35") (pin "2") (pinfunction "2_2") (pintype "input"))
      (node (ref "R38") (pin "1") (pinfunction "1_1") (pintype "input"))
      (node (ref "R4") (pin "1") (pinfunction "1_1") (pintype "input"))
      (node (ref "SW2") (pin "2") (pinfunction "2_2") (pintype "input"))
      (node (ref "SW3") (pin "2") (pinfunction "2_2") (pintype "input"))
      (node (ref "SW4") (pin "2") (pinfunction "2_2") (pintype "input"))
      (node (ref "SW5") (pin "2") (pinfunction "2_2") (pintype "input"))
      (node (ref "U1") (pin "2") (pinfunction "2_2") (pintype "unspecified"))
      (node (ref "U10") (pin "2") (pinfunction "GND_2") (pintype "unspecified"))
      (node (ref "U11") (pin "2") (pinfunction "GND_2") (pintype "unspecified"))
      (node (ref "U3") (pin "5") (pinfunction "5_5") (pintype "unspecified"))
      (node (ref "U3") (pin "6") (pinfunction "6_6") (pintype "unspecified"))
      (node (ref "U5") (pin "2") (pinfunction "GND_2") (pintype "unspecified"))
      (node (ref "U7") (pin "0") (pinfunction "EP/GND_0") (pintype "unspecified"))
      (node (ref "U7") (pin "7") (pinfunction "GND_7") (pintype "unspecified"))
      (node (ref "U8") (pin "1") (pinfunction "-_1") (pintype "input"))
      (node (ref "U?1") (pin "1") (pinfunction "GND_1") (pintype "input"))
      (node (ref "U?1") (pin "2") (pinfunction "GND_2") (pintype "input"))
      (node (ref "电机信号1") (pin "3") (pinfunction "3_3") (pintype "unspecified"))
      (node (ref "电机信号1") (pin "4") (pinfunction "4_4") (pintype "unspecified"))
      (node (ref "电机信号2") (pin "3") (pinfunction "3_3") (pintype "unspecified"))
      (node (ref "电机信号2") (pin "4") (pinfunction "4_4") (pintype "unspecified"))
      (node (ref "编码器1") (pin "1") (pinfunction "1_1") (pintype "unspecified"))
      (node (ref "编码器2") (pin "1") (pinfunction "1_1") (pintype "unspecified"))
      (node (ref "编码器3") (pin "1") (pinfunction "1_1") (pintype "unspecified"))
      (node (ref "编码器4") (pin "1") (pinfunction "1_1") (pintype "unspecified"))
    )
    (net (code "80") (name "Net-(BUZZER1-+)") (class "Default")
      (node (ref "BUZZER1") (pin "1") (pinfunction "+_1") (pintype "unspecified"))
      (node (ref "R17") (pin "2") (pinfunction "2_2") (pintype "input"))
    )
    (net (code "81") (name "Net-(BUZZER1--)") (class "Default")
      (node (ref "BUZZER1") (pin "2") (pinfunction "-_2") (pintype "unspecified"))
      (node (ref "Q2") (pin "3") (pinfunction "C_3") (pintype "unspecified"))
    )
    (net (code "82") (name "Net-(C20-Pad2)") (class "Default")
      (node (ref "C20") (pin "2") (pinfunction "2_2") (pintype "input"))
      (node (ref "R13") (pin "2") (pinfunction "2_2") (pintype "input"))
    )
    (net (code "83") (name "Net-(D2-A)") (class "Default")
      (node (ref "C13") (pin "2") (pinfunction "2_2") (pintype "input"))
      (node (ref "D2") (pin "2") (pinfunction "A_2") (pintype "unspecified"))
      (node (ref "L2") (pin "2") (pinfunction "2_2") (pintype "unspecified"))
    )
    (net (code "84") (name "Net-(D3-PadA)") (class "Default")
      (node (ref "D3") (pin "A") (pinfunction "A_A") (pintype "unspecified"))
      (node (ref "R2") (pin "1") (pinfunction "1_1") (pintype "input"))
      (node (ref "SW6") (pin "3") (pinfunction "3_3") (pintype "unspecified"))
    )
    (net (code "85") (name "Net-(LED1-A)") (class "Default")
      (node (ref "LED1") (pin "2") (pinfunction "A_2") (pintype "input"))
      (node (ref "R8") (pin "1") (pinfunction "1_1") (pintype "input"))
    )
    (net (code "86") (name "Net-(LED2-A)") (class "Default")
      (node (ref "LED2") (pin "2") (pinfunction "A_2") (pintype "input"))
      (node (ref "R9") (pin "1") (pinfunction "1_1") (pintype "input"))
    )
    (net (code "87") (name "Net-(LED3-A)") (class "Default")
      (node (ref "LED3") (pin "2") (pinfunction "A_2") (pintype "input"))
      (node (ref "R10") (pin "1") (pinfunction "1_1") (pintype "input"))
    )
    (net (code "88") (name "Net-(LED4-A)") (class "Default")
      (node (ref "LED4") (pin "2") (pinfunction "A_2") (pintype "input"))
      (node (ref "R11") (pin "1") (pinfunction "1_1") (pintype "input"))
    )
    (net (code "89") (name "Net-(LED5-A)") (class "Default")
      (node (ref "LED5") (pin "2") (pinfunction "A_2") (pintype "input"))
      (node (ref "R12") (pin "1") (pinfunction "1_1") (pintype "input"))
    )
    (net (code "90") (name "Net-(Q2-B)") (class "Default")
      (node (ref "Q2") (pin "2") (pinfunction "B_2") (pintype "unspecified"))
      (node (ref "R34") (pin "2") (pinfunction "2_2") (pintype "input"))
    )
    (net (code "91") (name "Net-(Q3-G)") (class "Default")
      (node (ref "Q3") (pin "2") (pinfunction "G_2") (pintype "unspecified"))
      (node (ref "SW6") (pin "2") (pinfunction "2_2") (pintype "unspecified"))
    )
    (net (code "92") (name "Net-(Q3-S)") (class "Default")
      (node (ref "D3") (pin "K") (pinfunction "K_K") (pintype "unspecified"))
      (node (ref "Q3") (pin "3") (pinfunction "S_3") (pintype "unspecified"))
      (node (ref "SW6") (pin "1") (pinfunction "1_1") (pintype "unspecified"))
      (node (ref "U8") (pin "2") (pinfunction "+_2") (pintype "input"))
    )
    (net (code "93") (name "Net-(R16-Pad1)") (class "Default")
      (node (ref "R16") (pin "1") (pinfunction "1_1") (pintype "input"))
      (node (ref "R27") (pin "2") (pinfunction "2_2") (pintype "input"))
    )
    (net (code "94") (name "Net-(R21-Pad1)") (class "Default")
      (node (ref "R21") (pin "1") (pinfunction "1_1") (pintype "input"))
      (node (ref "SW2") (pin "1") (pinfunction "1_1") (pintype "input"))
    )
    (net (code "95") (name "Net-(R22-Pad1)") (class "Default")
      (node (ref "R22") (pin "1") (pinfunction "1_1") (pintype "input"))
      (node (ref "电机信号1") (pin "2") (pinfunction "2_2") (pintype "unspecified"))
    )
    (net (code "96") (name "Net-(R23-Pad2)") (class "Default")
      (node (ref "R23") (pin "2") (pinfunction "2_2") (pintype "input"))
      (node (ref "电机信号1") (pin "6") (pinfunction "6_6") (pintype "unspecified"))
    )
    (net (code "97") (name "Net-(R24-Pad1)") (class "Default")
      (node (ref "R24") (pin "1") (pinfunction "1_1") (pintype "input"))
      (node (ref "电机信号1") (pin "1") (pinfunction "1_1") (pintype "unspecified"))
    )
    (net (code "98") (name "Net-(R25-Pad1)") (class "Default")
      (node (ref "R25") (pin "1") (pinfunction "1_1") (pintype "input"))
      (node (ref "电机信号1") (pin "5") (pinfunction "5_5") (pintype "unspecified"))
    )
    (net (code "99") (name "Net-(R26-Pad1)") (class "Default")
      (node (ref "R26") (pin "1") (pinfunction "1_1") (pintype "input"))
      (node (ref "电机信号2") (pin "2") (pinfunction "2_2") (pintype "unspecified"))
    )
    (net (code "100") (name "Net-(R28-Pad1)") (class "Default")
      (node (ref "R28") (pin "1") (pinfunction "1_1") (pintype "input"))
      (node (ref "电机信号2") (pin "1") (pinfunction "1_1") (pintype "unspecified"))
    )
    (net (code "101") (name "Net-(R29-Pad1)") (class "Default")
      (node (ref "R29") (pin "1") (pinfunction "1_1") (pintype "input"))
      (node (ref "电机信号2") (pin "5") (pinfunction "5_5") (pintype "unspecified"))
    )
    (net (code "102") (name "Net-(R30-Pad1)") (class "Default")
      (node (ref "R30") (pin "1") (pinfunction "1_1") (pintype "input"))
      (node (ref "SW3") (pin "1") (pinfunction "1_1") (pintype "input"))
    )
    (net (code "103") (name "Net-(R31-Pad1)") (class "Default")
      (node (ref "R31") (pin "1") (pinfunction "1_1") (pintype "input"))
      (node (ref "SW4") (pin "1") (pinfunction "1_1") (pintype "input"))
    )
    (net (code "104") (name "Net-(R33-Pad1)") (class "Default")
      (node (ref "R33") (pin "1") (pinfunction "1_1") (pintype "input"))
      (node (ref "SW5") (pin "1") (pinfunction "1_1") (pintype "input"))
    )
    (net (code "105") (name "Net-(R5327-Pad2)") (class "Default")
      (node (ref "R5327") (pin "2") (pinfunction "2_2") (pintype "input"))
      (node (ref "电机信号2") (pin "6") (pinfunction "6_6") (pintype "unspecified"))
    )
    (net (code "106") (name "Net-(U5-ISET)") (class "Default")
      (node (ref "R38") (pin "2") (pinfunction "2_2") (pintype "input"))
      (node (ref "U5") (pin "3") (pinfunction "ISET_3") (pintype "unspecified"))
    )
    (net (code "107") (name "Net-(U7-BOOT)") (class "Default")
      (node (ref "C12") (pin "1") (pinfunction "1_1") (pintype "input"))
      (node (ref "U7") (pin "1") (pinfunction "BOOT_1") (pintype "unspecified"))
    )
    (net (code "108") (name "Net-(U7-COMP)") (class "Default")
      (node (ref "R13") (pin "1") (pinfunction "1_1") (pintype "input"))
      (node (ref "U7") (pin "6") (pinfunction "COMP_6") (pintype "unspecified"))
    )
    (net (code "109") (name "Net-(U7-FB)") (class "Default")
      (node (ref "R18") (pin "2") (pinfunction "2_2") (pintype "input"))
      (node (ref "R27") (pin "1") (pinfunction "1_1") (pintype "input"))
      (node (ref "U7") (pin "5") (pinfunction "FB_5") (pintype "unspecified"))
    )
    (net (code "110") (name "Net-(U7-RT{slash}CLK)") (class "Default")
      (node (ref "R4") (pin "2") (pinfunction "2_2") (pintype "input"))
      (node (ref "U7") (pin "4") (pinfunction "RT/CLK_4") (pintype "unspecified"))
    )
    (net (code "111") (name "Net-(U7-SW)") (class "Default")
      (node (ref "C12") (pin "2") (pinfunction "2_2") (pintype "input"))
      (node (ref "L2") (pin "1") (pinfunction "1_1") (pintype "unspecified"))
      (node (ref "U7") (pin "8") (pinfunction "SW_8") (pintype "unspecified"))
    )
    (net (code "112") (name "Net-(U?1-CR)") (class "Default")
      (node (ref "R36") (pin "1") (pinfunction "1_1") (pintype "input"))
      (node (ref "R37") (pin "1") (pinfunction "1_1") (pintype "input"))
      (node (ref "U?1") (pin "9") (pinfunction "CR_9") (pintype "input"))
    )
    (net (code "113") (name "VCC-5V") (class "Default")
      (node (ref "C11") (pin "1") (pinfunction "1_1") (pintype "input"))
      (node (ref "C18") (pin "1") (pinfunction "1_1") (pintype "input"))
      (node (ref "D2") (pin "1") (pinfunction "C_1") (pintype "unspecified"))
      (node (ref "R16") (pin "2") (pinfunction "2_2") (pintype "input"))
      (node (ref "R9") (pin "2") (pinfunction "2_2") (pintype "input"))
      (node (ref "U5") (pin "5") (pinfunction "VIN_5") (pintype "unspecified"))
      (node (ref "U?1") (pin "5") (pinfunction "5V_5") (pintype "input"))
      (node (ref "U?1") (pin "6") (pinfunction "5V_6") (pintype "input"))
    )
    (net (code "114") (name "VCC-5V-EXT") (class "Default")
      (node (ref "C23") (pin "2") (pinfunction "2_2") (pintype "input"))
      (node (ref "CN1") (pin "2") (pinfunction "2_2") (pintype "unspecified"))
      (node (ref "H1") (pin "1") (pinfunction "1_1") (pintype "unspecified"))
      (node (ref "H2") (pin "1") (pinfunction "1_1") (pintype "unspecified"))
      (node (ref "R8") (pin "2") (pinfunction "2_2") (pintype "input"))
      (node (ref "U3") (pin "7") (pinfunction "7_7") (pintype "unspecified"))
      (node (ref "U5") (pin "1") (pinfunction "VOUT_1") (pintype "unspecified"))
    )
    (net (code "115") (name "VCCBAT") (class "Default")
      (node (ref "C15") (pin "1") (pinfunction "1_1") (pintype "input"))
      (node (ref "C16") (pin "2") (pinfunction "2_2") (pintype "input"))
      (node (ref "C17") (pin "2") (pinfunction "2_2") (pintype "input"))
      (node (ref "CN3") (pin "1") (pinfunction "1_1") (pintype "unspecified"))
      (node (ref "CN4") (pin "1") (pinfunction "1_1") (pintype "unspecified"))
      (node (ref "Q3") (pin "1") (pinfunction "D_1") (pintype "unspecified"))
      (node (ref "U7") (pin "2") (pinfunction "VIN_2") (pintype "unspecified"))
      (node (ref "U7") (pin "3") (pinfunction "EN_3") (pintype "unspecified"))
    )
    (net (code "116") (name "VCC_5V") (class "Default")
      (node (ref "C14") (pin "2") (pinfunction "2_2") (pintype "input"))
      (node (ref "C7") (pin "2") (pinfunction "2_2") (pintype "input"))
      (node (ref "U10") (pin "1") (pinfunction "VIN_1") (pintype "unspecified"))
      (node (ref "U11") (pin "1") (pinfunction "VIN_1") (pintype "unspecified"))
    )
    (net (code "117") (name "VCC_SERVO") (class "Default")
      (node (ref "R12") (pin "2") (pinfunction "2_2") (pintype "input"))
    )
    (net (code "118") (name "unconnected-(CN1-Pad9)") (class "Default")
      (node (ref "CN1") (pin "9") (pinfunction "9_9") (pintype "unspecified+no_connect"))
    )
    (net (code "119") (name "unconnected-(CN2-Pad7)") (class "Default")
      (node (ref "CN2") (pin "7") (pinfunction "7_7") (pintype "unspecified+no_connect"))
    )
    (net (code "120") (name "unconnected-(CN2-Pad8)") (class "Default")
      (node (ref "CN2") (pin "8") (pinfunction "8_8") (pintype "unspecified+no_connect"))
    )
    (net (code "121") (name "unconnected-(U3-Pad2)") (class "Default")
      (node (ref "U3") (pin "2") (pinfunction "2_2") (pintype "unspecified+no_connect"))
    )
    (net (code "122") (name "unconnected-(U10-NC-Pad4)") (class "Default")
      (node (ref "U10") (pin "4") (pinfunction "NC_4") (pintype "unspecified+no_connect"))
    )
    (net (code "123") (name "unconnected-(U11-NC-Pad4)") (class "Default")
      (node (ref "U11") (pin "4") (pinfunction "NC_4") (pintype "unspecified+no_connect"))
    )
    (net (code "124") (name "unconnected-(U?1-2DN-Pad22)") (class "Default")
      (node (ref "U?1") (pin "22") (pinfunction "2DN_22") (pintype "input"))
    )
    (net (code "125") (name "unconnected-(U?1-2DP-Pad21)") (class "Default")
      (node (ref "U?1") (pin "21") (pinfunction "2DP_21") (pintype "input"))
    )
    (net (code "126") (name "unconnected-(U?1-3V3-Pad3)") (class "Default")
      (node (ref "U?1") (pin "3") (pinfunction "3V3_3") (pintype "input+no_connect"))
    )
    (net (code "127") (name "unconnected-(U?1-3V3-Pad4)") (class "Default")
      (node (ref "U?1") (pin "4") (pinfunction "3V3_4") (pintype "input+no_connect"))
    )
    (net (code "128") (name "unconnected-(U?1-B16-Pad32)") (class "Default")
      (node (ref "U?1") (pin "32") (pinfunction "B16_32") (pintype "input"))
    )
    (net (code "129") (name "unconnected-(U?1-B17-Pad31)") (class "Default")
      (node (ref "U?1") (pin "31") (pinfunction "B17_31") (pintype "input"))
    )
    (net (code "130") (name "unconnected-(U?1-C12-Pad70)") (class "Default")
      (node (ref "U?1") (pin "70") (pinfunction "C12_70") (pintype "input"))
    )
    (net (code "131") (name "unconnected-(U?1-C13-Pad67)") (class "Default")
      (node (ref "U?1") (pin "67") (pinfunction "C13_67") (pintype "input"))
    )
    (net (code "132") (name "unconnected-(U?1-C14-Pad68)") (class "Default")
      (node (ref "U?1") (pin "68") (pinfunction "C14_68") (pintype "input"))
    )
    (net (code "133") (name "unconnected-(U?1-C15-Pad65)") (class "Default")
      (node (ref "U?1") (pin "65") (pinfunction "C15_65") (pintype "input"))
    )
    (net (code "134") (name "unconnected-(U?1-D4-Pad10)") (class "Default")
      (node (ref "U?1") (pin "10") (pinfunction "D4_10") (pintype "input+no_connect"))
    )
    (net (code "135") (name "unconnected-(U?1-D27-Pad81)") (class "Default")
      (node (ref "U?1") (pin "81") (pinfunction "D27_81") (pintype "input"))
    )
    (net (code "136") (name "unconnected-(U?1-GND-Pad83)") (class "Default")
      (node (ref "U?1") (pin "83") (pinfunction "GND_83") (pintype "input"))
    )
    (net (code "137") (name "unconnected-(U?1-OF-Pad7)") (class "Default")
      (node (ref "U?1") (pin "7") (pinfunction "OF_7") (pintype "input+no_connect"))
    )
    (net (code "138") (name "unconnected-(U?1-WU-Pad8)") (class "Default")
      (node (ref "U?1") (pin "8") (pinfunction "WU_8") (pintype "input+no_connect"))
    )
    (net (code "139") (name "unconnected-(编码器1-Pad5)") (class "Default")
      (node (ref "编码器1") (pin "5") (pinfunction "5_5") (pintype "unspecified+no_connect"))
    )
    (net (code "140") (name "unconnected-(编码器1-Pad6)") (class "Default")
      (node (ref "编码器1") (pin "6") (pinfunction "6_6") (pintype "unspecified+no_connect"))
    )
    (net (code "141") (name "unconnected-(编码器2-Pad5)") (class "Default")
      (node (ref "编码器2") (pin "5") (pinfunction "5_5") (pintype "unspecified+no_connect"))
    )
    (net (code "142") (name "unconnected-(编码器2-Pad6)") (class "Default")
      (node (ref "编码器2") (pin "6") (pinfunction "6_6") (pintype "unspecified+no_connect"))
    )
    (net (code "143") (name "unconnected-(编码器3-Pad5)") (class "Default")
      (node (ref "编码器3") (pin "5") (pinfunction "5_5") (pintype "unspecified+no_connect"))
    )
    (net (code "144") (name "unconnected-(编码器3-Pad6)") (class "Default")
      (node (ref "编码器3") (pin "6") (pinfunction "6_6") (pintype "unspecified+no_connect"))
    )
    (net (code "145") (name "unconnected-(编码器4-Pad5)") (class "Default")
      (node (ref "编码器4") (pin "5") (pinfunction "5_5") (pintype "unspecified+no_connect"))
    )
    (net (code "146") (name "unconnected-(编码器4-Pad6)") (class "Default")
      (node (ref "编码器4") (pin "6") (pinfunction "6_6") (pintype "unspecified+no_connect"))
    )
  )
)
